# LcsNodes-Building-Block-Power-Supply-LM2.net
KiCad netlist of a schematic drawn in EasyEDA
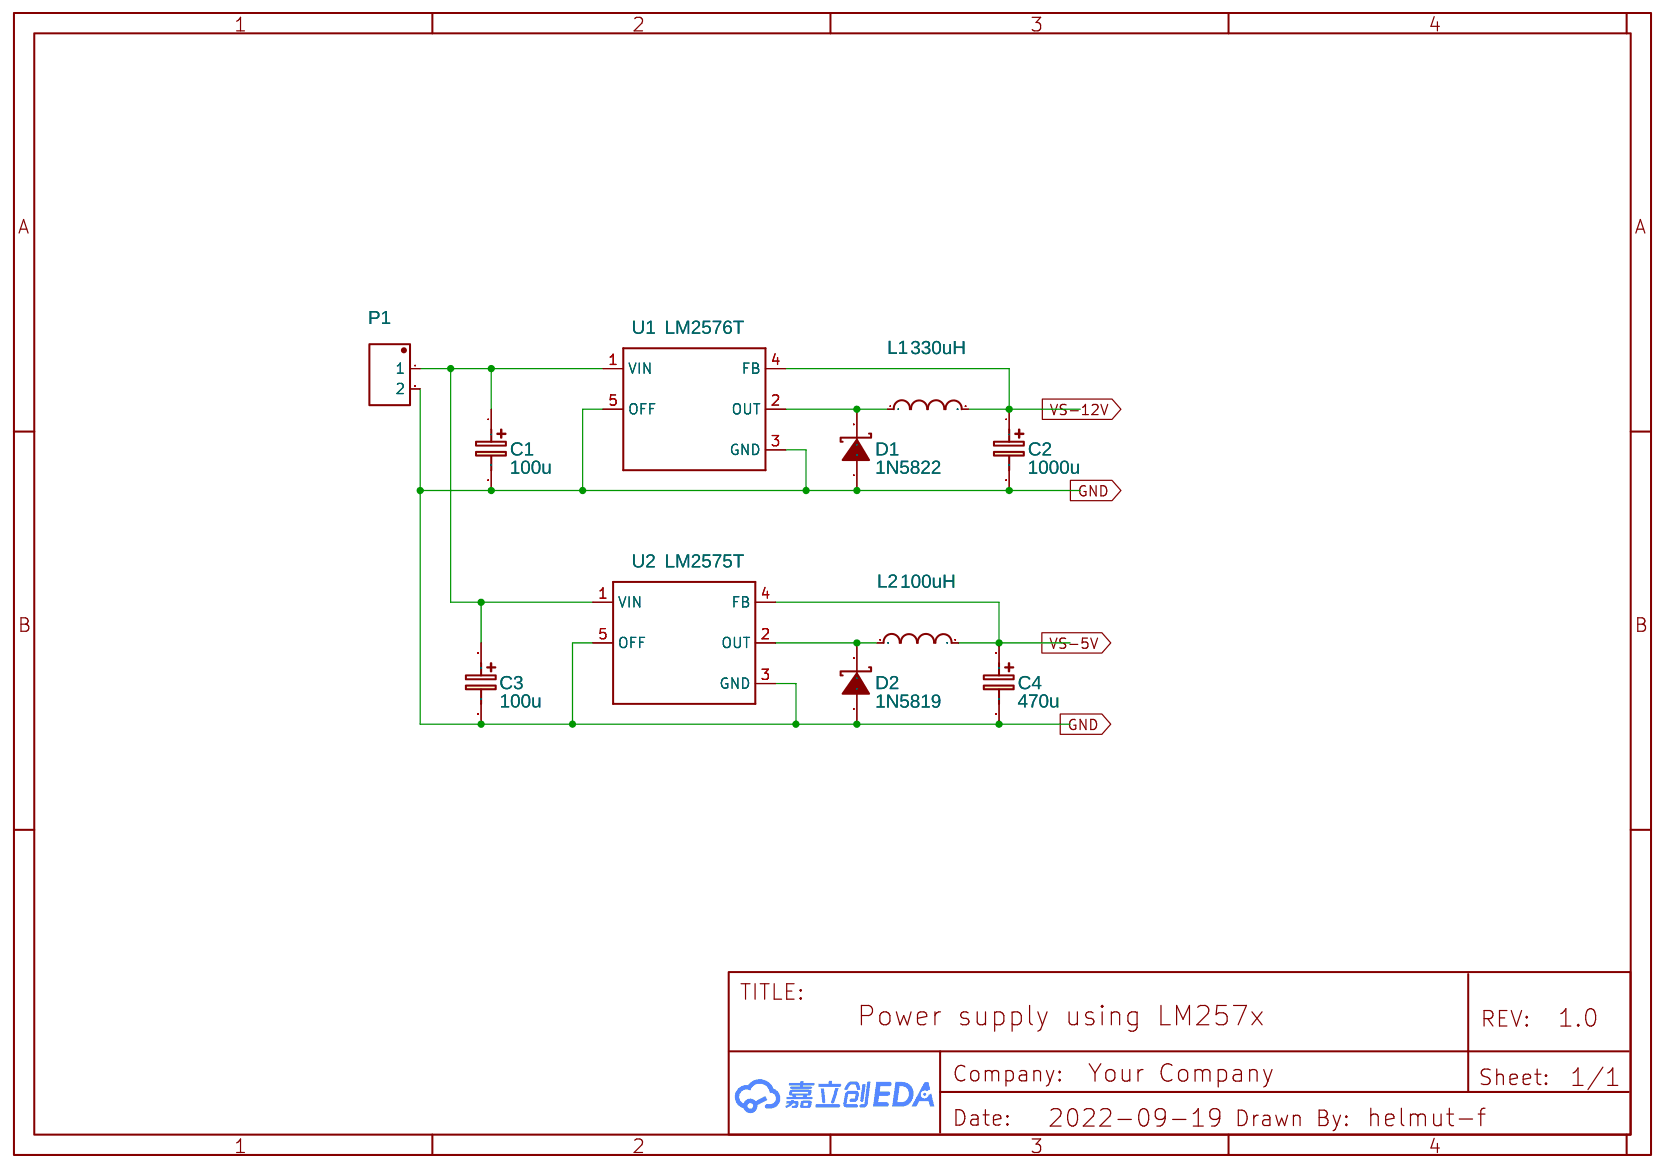
[diagram p0: schematic sheet]

(export (version "E")
  (design (tool "Eeschema 10.0.6"))
  (components
    (comp (ref "C1") (value "100u") (libsource (lib "") (part "CE_TH_D4.0×F1.5_EU")))
    (comp (ref "C2") (value "1000u") (libsource (lib "") (part "CE_TH_D4.0×F1.5_EU")))
    (comp (ref "C3") (value "100u") (libsource (lib "") (part "CE_TH_D4.0×F1.5_EU_1")))
    (comp (ref "C4") (value "470u") (libsource (lib "") (part "CE_TH_D4.0×F1.5_EU_1")))
    (comp (ref "D1")
      (value "1N5822")
      (fields (field (name "BOM_Supplier Part") "C2476"))
      (libsource (lib "") (part "1N5822"))
    )
    (comp (ref "D2")
      (value "1N5819")
      (fields (field (name "BOM_Supplier Part") "C110032"))
      (libsource (lib "") (part "1N5819"))
    )
    (comp (ref "L1")
      (value "330uH")
      (fields (field (name "BOM_Manufacturer Part") "Power inductorSMRH5D28-8R2NT"))
      (libsource (lib "") (part "Leaded Power Inductors 330uH, 1.1A"))
    )
    (comp (ref "L2")
      (value "100uH")
      (fields (field (name "BOM_Manufacturer Part") "Power inductorSMRH5D28-8R2NT"))
      (libsource (lib "") (part "Leaded Power Inductors 330uH, 1.1A"))
    )
    (comp (ref "P1")
      (value "Terminal_block_2P_2.54")
      (fields
        (field (name "BOM_Manufacturer Part") "MTP0.5/4-2.54")
        (field (name "BOM_Supplier Part") "3041414")
      )
      (libsource (lib "") (part "Terminal_block_2P_2.54"))
    )
    (comp (ref "U1") (value "LM2576T") (libsource (lib "") (part "LM2576T")))
    (comp (ref "U2") (value "LM2575T") (libsource (lib "") (part "LM2576T")))
  )
  (nets
    (net (code "2") (name "Net-(D1-A)") (class "Default")
      (node (ref "C1") (pin "2") (pinfunction "2_2") (pintype "unspecified"))
      (node (ref "C2") (pin "2") (pinfunction "2_2") (pintype "unspecified"))
      (node (ref "C3") (pin "2") (pinfunction "2_2") (pintype "unspecified"))
      (node (ref "C4") (pin "2") (pinfunction "2_2") (pintype "unspecified"))
      (node (ref "D1") (pin "1") (pinfunction "A_1") (pintype "unspecified"))
      (node (ref "D2") (pin "1") (pinfunction "A_1") (pintype "unspecified"))
      (node (ref "P1") (pin "2") (pinfunction "2_2") (pintype "unspecified"))
      (node (ref "U1") (pin "3") (pinfunction "GND_3") (pintype "passive"))
      (node (ref "U1") (pin "5") (pinfunction "OFF_5") (pintype "input"))
      (node (ref "U2") (pin "3") (pinfunction "GND_3") (pintype "passive"))
      (node (ref "U2") (pin "5") (pinfunction "OFF_5") (pintype "input"))
    )
    (net (code "3") (name "Net-(D1-K)") (class "Default")
      (node (ref "D1") (pin "2") (pinfunction "K_2") (pintype "unspecified"))
      (node (ref "L1") (pin "1") (pinfunction "1_1") (pintype "unspecified"))
      (node (ref "U1") (pin "2") (pinfunction "OUT_2") (pintype "output"))
    )
    (net (code "4") (name "Net-(D2-K)") (class "Default")
      (node (ref "D2") (pin "2") (pinfunction "K_2") (pintype "unspecified"))
      (node (ref "L2") (pin "1") (pinfunction "1_1") (pintype "unspecified"))
      (node (ref "U2") (pin "2") (pinfunction "OUT_2") (pintype "output"))
    )
    (net (code "5") (name "Net-(U1-FB)") (class "Default")
      (node (ref "C2") (pin "1") (pinfunction "1_1") (pintype "unspecified"))
      (node (ref "L1") (pin "2") (pinfunction "2_2") (pintype "unspecified"))
      (node (ref "U1") (pin "4") (pinfunction "FB_4") (pintype "input"))
    )
    (net (code "6") (name "Net-(U1-VIN)") (class "Default")
      (node (ref "C1") (pin "1") (pinfunction "1_1") (pintype "unspecified"))
      (node (ref "C3") (pin "1") (pinfunction "1_1") (pintype "unspecified"))
      (node (ref "P1") (pin "1") (pinfunction "1_1") (pintype "unspecified"))
      (node (ref "U1") (pin "1") (pinfunction "VIN_1") (pintype "passive"))
      (node (ref "U2") (pin "1") (pinfunction "VIN_1") (pintype "passive"))
    )
    (net (code "7") (name "Net-(U2-FB)") (class "Default")
      (node (ref "C4") (pin "1") (pinfunction "1_1") (pintype "unspecified"))
      (node (ref "L2") (pin "2") (pinfunction "2_2") (pintype "unspecified"))
      (node (ref "U2") (pin "4") (pinfunction "FB_4") (pintype "input"))
    )
  )
)
